# Schematic_Altium.net
KiCad netlist of a schematic drawn in Altium Designer
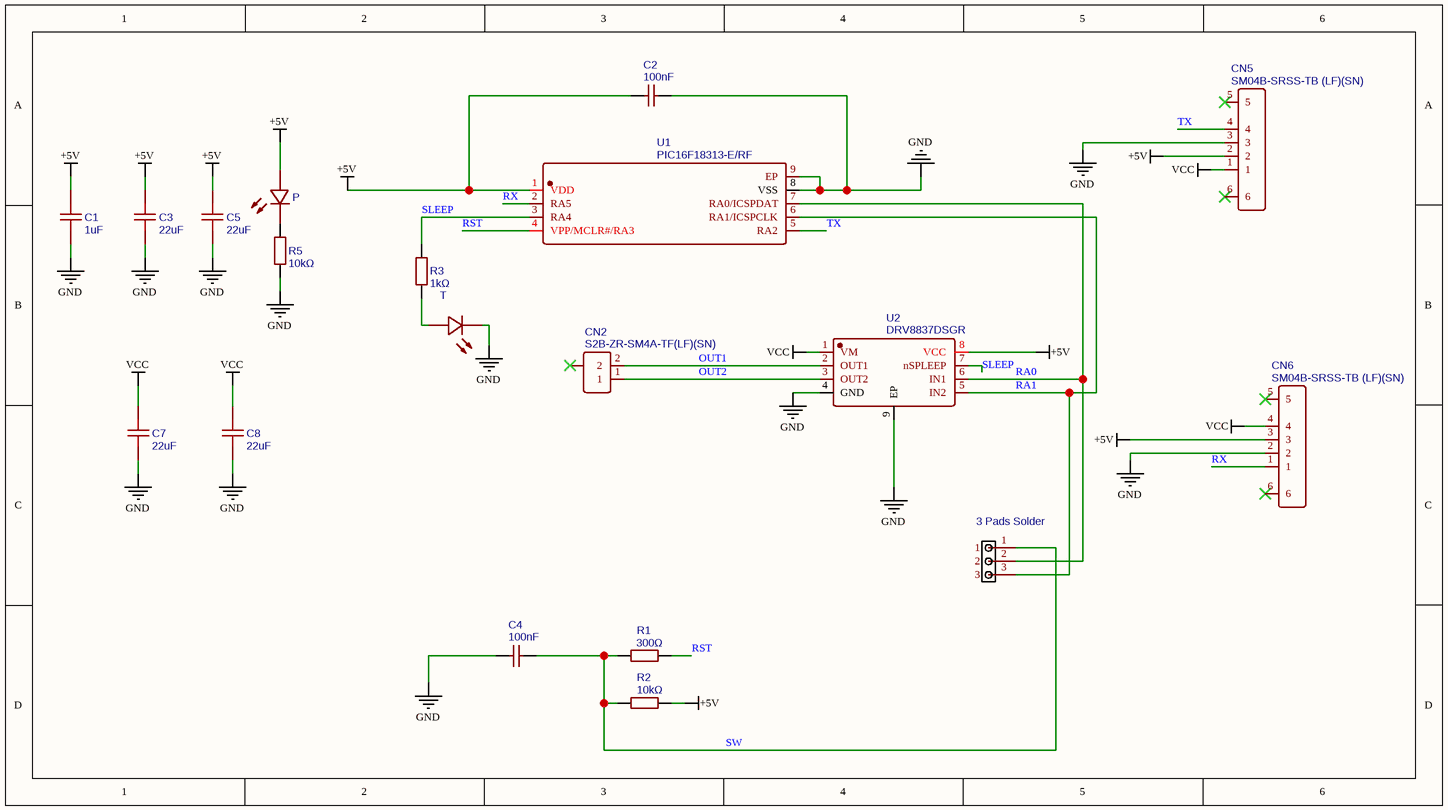
[diagram p0: Schematic_Altium.schdoc]

(export (version "E")
  (design (tool "Eeschema 10.0.6"))
  (components
    (comp (ref "C1")
      (value "1uF")
      (fields
        (field (name "MANUFACTURER") "SAMSUNG(三星)")
        (field (name "MANUFACTURER PART") "CL05A105KA5NQNC")
      )
      (libsource (lib "altium-import") (part "root_1_1uF_"))
    )
    (comp (ref "C2")
      (value "100nF")
      (fields
        (field (name "MANUFACTURER PART") "CL05B104KO5NNNC")
        (field (name "MANUFACTURER") "SAMSUNG(三星)")
      )
      (libsource (lib "altium-import") (part "root_0_100nF_"))
    )
    (comp (ref "C3")
      (value "22uF")
      (fields
        (field (name "MANUFACTURER") "muRata(村田)")
        (field (name "MANUFACTURER PART") "GRM155C80E226ME11D")
        (field (name "CONTRIBUTOR") "LCSC")
      )
      (libsource (lib "altium-import") (part "root_1_22uF_"))
    )
    (comp (ref "C4")
      (value "100nF")
      (fields
        (field (name "MANUFACTURER PART") "CL05B104KO5NNNC")
        (field (name "MANUFACTURER") "SAMSUNG(三星)")
      )
      (libsource (lib "altium-import") (part "root_0_100nF_"))
    )
    (comp (ref "C5")
      (value "22uF")
      (fields
        (field (name "MANUFACTURER") "muRata(村田)")
        (field (name "MANUFACTURER PART") "GRM155C80E226ME11D")
        (field (name "CONTRIBUTOR") "LCSC")
      )
      (libsource (lib "altium-import") (part "root_1_22uF_"))
    )
    (comp (ref "C7")
      (value "22uF")
      (fields
        (field (name "MANUFACTURER") "muRata(村田)")
        (field (name "MANUFACTURER PART") "GRM155C80E226ME11D")
        (field (name "CONTRIBUTOR") "LCSC")
      )
      (libsource (lib "altium-import") (part "root_1_22uF_"))
    )
    (comp (ref "C8")
      (value "22uF")
      (fields
        (field (name "MANUFACTURER") "muRata(村田)")
        (field (name "MANUFACTURER PART") "GRM155C80E226ME11D")
        (field (name "CONTRIBUTOR") "LCSC")
      )
      (libsource (lib "altium-import") (part "root_1_22uF_"))
    )
    (comp (ref "CN2")
      (value "S2B-ZR-SM4A-TF(LF)(SN)")
      (fields (field (name "MANUFACTURER") "JST") (field (name "CONTRIBUTOR") "LCSC"))
      (libsource (lib "altium-import") (part "root_2_S2B-ZR-SM4A-TF(LF)(SN)_"))
    )
    (comp (ref "CN3")
      (value "3 Pads Solder")
      (fields (field (name "MANUFACTURER PART") "3 pads") (field (name "CONTRIBUTOR") "JonnyED"))
      (libsource (lib "altium-import") (part "root_0_3 Pads Solder_"))
    )
    (comp (ref "CN5")
      (value "SM04B-SRSS-TB (LF)(SN)")
      (fields
        (field (name "MANUFACTURER") "JST")
        (field (name "MANUFACTURER PART") "SM04B-SRSS-TB(LF)(SN)")
        (field (name "CONTRIBUTOR") "LCSC")
      )
      (libsource (lib "altium-import") (part "root_1_SM04B-SRSS-TB (LF)(SN)_"))
    )
    (comp (ref "CN6")
      (value "SM04B-SRSS-TB (LF)(SN)")
      (fields
        (field (name "MANUFACTURER") "JST")
        (field (name "MANUFACTURER PART") "SM04B-SRSS-TB(LF)(SN)")
        (field (name "CONTRIBUTOR") "LCSC")
      )
      (libsource (lib "altium-import") (part "root_1_SM04B-SRSS-TB (LF)(SN)_"))
    )
    (comp (ref "P")
      (value "19-213/GVC-CK0LLY/3T(HW)")
      (fields (field (name "MANUFACTURER") "Everlight Elec") (field (name "CONTRIBUTOR") "LCSC"))
      (libsource (lib "altium-import") (part "root_1_19-213/GVC-CK0LLY/3T(HW)_"))
    )
    (comp (ref "R1")
      (value "300Ω")
      (fields
        (field (name "MANUFACTURER") "UNI-ROYAL(厚声)")
        (field (name "MANUFACTURER PART") "0402WGF3000TCE")
      )
      (libsource (lib "altium-import") (part "root_0_300Ω_"))
    )
    (comp (ref "R2")
      (value "10kΩ")
      (fields
        (field (name "MANUFACTURER") "UNI-ROYAL(厚声)")
        (field (name "MANUFACTURER PART") "0402WGF1002TCE")
      )
      (libsource (lib "altium-import") (part "root_0_10kΩ_"))
    )
    (comp (ref "R3")
      (value "1kΩ")
      (fields
        (field (name "MANUFACTURER") "UNI-ROYAL(厚声)")
        (field (name "MANUFACTURER PART") "0402WGF1001TCE")
      )
      (libsource (lib "altium-import") (part "root_3_1kΩ_"))
    )
    (comp (ref "R5")
      (value "10kΩ")
      (fields
        (field (name "MANUFACTURER") "UNI-ROYAL(厚声)")
        (field (name "MANUFACTURER PART") "0402WGF1002TCE")
      )
      (libsource (lib "altium-import") (part "root_1_10kΩ_"))
    )
    (comp (ref "T")
      (value "19-213/GVC-CK0LLY/3T(HW)")
      (fields (field (name "MANUFACTURER") "Everlight Elec") (field (name "CONTRIBUTOR") "LCSC"))
      (libsource (lib "altium-import") (part "root_2_19-213/GVC-CK0LLY/3T(HW)_"))
    )
    (comp (ref "U1")
      (value "PIC16F18313-E/RF")
      (fields (field (name "MANUFACTURER") "MICROCHIP(美国微芯)") (field (name "CONTRIBUTOR") "lcsc"))
      (libsource (lib "altium-import") (part "root_0_PIC16F18313-E/RF_"))
    )
    (comp (ref "U2")
      (value "DRV8837DSGR")
      (fields (field (name "MANUFACTURER") "TI(德州仪器)"))
      (libsource (lib "altium-import") (part "root_0_DRV8837DSGR_"))
    )
  )
  (nets
    (net (code "1") (name "+5V") (class "Default")
      (node (ref "C1") (pin "2") (pinfunction "2_2") (pintype "passive"))
      (node (ref "C2") (pin "1") (pinfunction "1_1") (pintype "passive"))
      (node (ref "C3") (pin "2") (pinfunction "2_2") (pintype "passive"))
      (node (ref "C5") (pin "2") (pinfunction "2_2") (pintype "passive"))
      (node (ref "CN5") (pin "2") (pinfunction "2_2") (pintype "passive"))
      (node (ref "CN6") (pin "3") (pinfunction "3_3") (pintype "passive"))
      (node (ref "P") (pin "1") (pinfunction "A_1") (pintype "passive"))
      (node (ref "R2") (pin "2") (pinfunction "2_2") (pintype "passive"))
      (node (ref "U1") (pin "1") (pinfunction "VDD_1") (pintype "passive"))
      (node (ref "U2") (pin "8") (pinfunction "VCC_8") (pintype "passive"))
    )
    (net (code "2") (name "/OUT1") (class "Default")
      (node (ref "CN2") (pin "2") (pinfunction "2_2") (pintype "passive"))
      (node (ref "U2") (pin "2") (pinfunction "OUT1_2") (pintype "passive"))
    )
    (net (code "3") (name "/OUT2") (class "Default")
      (node (ref "CN2") (pin "1") (pinfunction "1_1") (pintype "passive"))
      (node (ref "U2") (pin "3") (pinfunction "OUT2_3") (pintype "passive"))
    )
    (net (code "4") (name "/RA0") (class "Default")
      (node (ref "CN3") (pin "2") (pinfunction "2_2") (pintype "passive"))
      (node (ref "U1") (pin "7") (pinfunction "RA0/ICSPDAT_7") (pintype "passive"))
      (node (ref "U2") (pin "6") (pinfunction "IN1_6") (pintype "passive"))
    )
    (net (code "5") (name "/RA1") (class "Default")
      (node (ref "CN3") (pin "3") (pinfunction "3_3") (pintype "passive"))
      (node (ref "U1") (pin "6") (pinfunction "RA1/ICSPCLK_6") (pintype "passive"))
      (node (ref "U2") (pin "5") (pinfunction "IN2_5") (pintype "passive"))
    )
    (net (code "6") (name "/RST") (class "Default")
      (node (ref "R1") (pin "2") (pinfunction "2_2") (pintype "passive"))
      (node (ref "U1") (pin "4") (pinfunction "VPP/MCLR#/RA3_4") (pintype "passive"))
    )
    (net (code "7") (name "/RX") (class "Default")
      (node (ref "CN6") (pin "1") (pinfunction "1_1") (pintype "passive"))
      (node (ref "U1") (pin "2") (pinfunction "RA5_2") (pintype "passive"))
    )
    (net (code "8") (name "/SLEEP") (class "Default")
      (node (ref "R3") (pin "1") (pinfunction "1_1") (pintype "passive"))
      (node (ref "U1") (pin "3") (pinfunction "RA4_3") (pintype "passive"))
      (node (ref "U2") (pin "7") (pinfunction "nSPLEEP_7") (pintype "passive"))
    )
    (net (code "9") (name "/SW") (class "Default")
      (node (ref "C4") (pin "2") (pinfunction "2_2") (pintype "passive"))
      (node (ref "CN3") (pin "1") (pinfunction "1_1") (pintype "passive"))
      (node (ref "R1") (pin "1") (pinfunction "1_1") (pintype "passive"))
      (node (ref "R2") (pin "1") (pinfunction "1_1") (pintype "passive"))
    )
    (net (code "10") (name "/TX") (class "Default")
      (node (ref "CN5") (pin "4") (pinfunction "4_4") (pintype "passive"))
      (node (ref "U1") (pin "5") (pinfunction "RA2_5") (pintype "passive"))
    )
    (net (code "11") (name "GND") (class "Default")
      (node (ref "C1") (pin "1") (pinfunction "1_1") (pintype "passive"))
      (node (ref "C2") (pin "2") (pinfunction "2_2") (pintype "passive"))
      (node (ref "C3") (pin "1") (pinfunction "1_1") (pintype "passive"))
      (node (ref "C4") (pin "1") (pinfunction "1_1") (pintype "passive"))
      (node (ref "C5") (pin "1") (pinfunction "1_1") (pintype "passive"))
      (node (ref "C7") (pin "1") (pinfunction "1_1") (pintype "passive"))
      (node (ref "C8") (pin "1") (pinfunction "1_1") (pintype "passive"))
      (node (ref "CN5") (pin "3") (pinfunction "3_3") (pintype "passive"))
      (node (ref "CN6") (pin "2") (pinfunction "2_2") (pintype "passive"))
      (node (ref "R5") (pin "1") (pinfunction "1_1") (pintype "passive"))
      (node (ref "T") (pin "2") (pinfunction "K_2") (pintype "passive"))
      (node (ref "U1") (pin "8") (pinfunction "VSS_8") (pintype "passive"))
      (node (ref "U1") (pin "9") (pinfunction "EP_9") (pintype "passive"))
      (node (ref "U2") (pin "4") (pinfunction "GND_4") (pintype "passive"))
      (node (ref "U2") (pin "9") (pinfunction "EP_9") (pintype "passive"))
    )
    (net (code "12") (name "Net-(P-K)") (class "Default")
      (node (ref "P") (pin "2") (pinfunction "K_2") (pintype "passive"))
      (node (ref "R5") (pin "2") (pinfunction "2_2") (pintype "passive"))
    )
    (net (code "13") (name "Net-(T-A)") (class "Default")
      (node (ref "R3") (pin "2") (pinfunction "2_2") (pintype "passive"))
      (node (ref "T") (pin "1") (pinfunction "A_1") (pintype "passive"))
    )
    (net (code "14") (name "VCC") (class "Default")
      (node (ref "C7") (pin "2") (pinfunction "2_2") (pintype "passive"))
      (node (ref "C8") (pin "2") (pinfunction "2_2") (pintype "passive"))
      (node (ref "CN5") (pin "1") (pinfunction "1_1") (pintype "passive"))
      (node (ref "CN6") (pin "4") (pinfunction "4_4") (pintype "passive"))
      (node (ref "U2") (pin "1") (pinfunction "VM_1") (pintype "passive"))
    )
    (net (code "15") (name "unconnected-(CN2-Pad0)") (class "Default")
      (node (ref "CN2") (pin "0") (pinfunction "0_0") (pintype "passive+no_connect"))
    )
    (net (code "16") (name "unconnected-(CN5-Pad5)") (class "Default")
      (node (ref "CN5") (pin "5") (pinfunction "5_5") (pintype "passive+no_connect"))
    )
    (net (code "17") (name "unconnected-(CN5-Pad6)") (class "Default")
      (node (ref "CN5") (pin "6") (pinfunction "6_6") (pintype "passive+no_connect"))
    )
    (net (code "18") (name "unconnected-(CN6-Pad5)") (class "Default")
      (node (ref "CN6") (pin "5") (pinfunction "5_5") (pintype "passive+no_connect"))
    )
    (net (code "19") (name "unconnected-(CN6-Pad6)") (class "Default")
      (node (ref "CN6") (pin "6") (pinfunction "6_6") (pintype "passive+no_connect"))
    )
  )
)
